# uC.net
KiCad netlist of a schematic drawn in Altium Designer
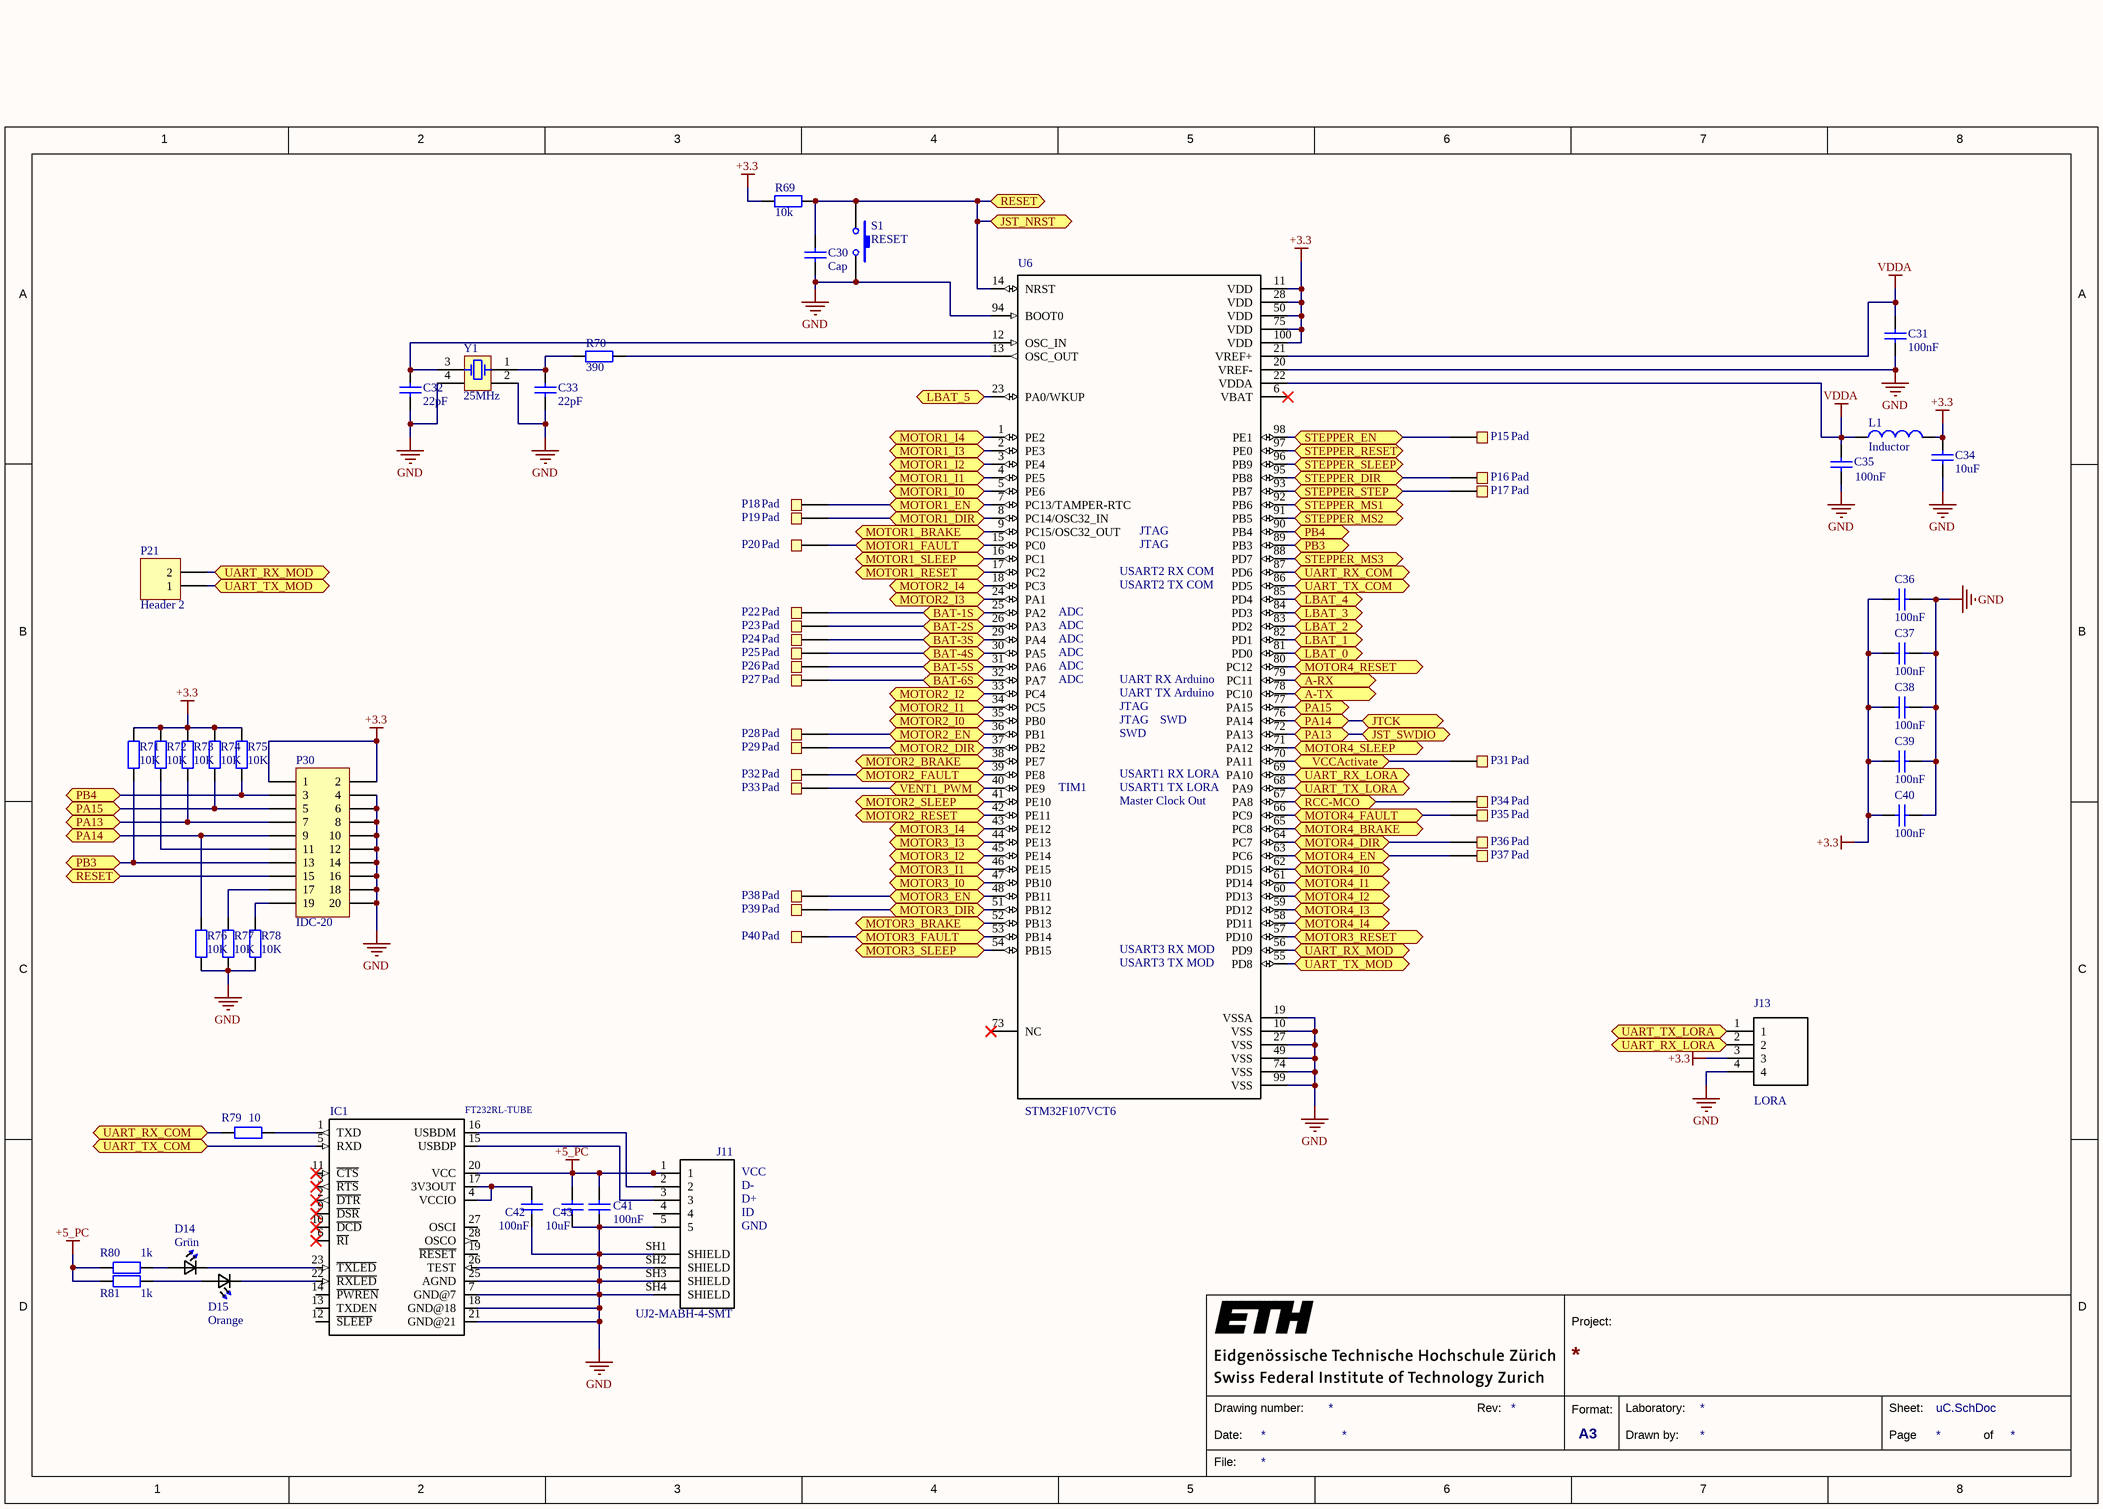
[diagram p0: uC.SchDoc]

(export (version "E")
  (design (tool "Eeschema 10.0.6"))
  (components
    (comp (ref "C30")
      (value "Cap")
      (footprint "CAP_0603i_1608m -N")
      (description "capacitor")
      (libsource (lib "IDSC std generic parts") (part "Cap"))
    )
    (comp (ref "C31")
      (value "100nF")
      (footprint "CAP_0603i_1608m -N")
      (description "capacitor")
      (libsource (lib "IDSC std generic parts") (part "Cap"))
    )
    (comp (ref "C32")
      (value "22pF")
      (footprint "CAP_0603i_1608m -N")
      (description "capacitor")
      (libsource (lib "IDSC std generic parts") (part "Cap"))
    )
    (comp (ref "C33")
      (value "22pF")
      (footprint "CAP_0603i_1608m -N")
      (description "capacitor")
      (libsource (lib "IDSC std generic parts") (part "Cap"))
    )
    (comp (ref "C34")
      (value "10uF")
      (footprint "CAP_0805i_2012m -N")
      (description "capacitor")
      (libsource (lib "IDSC std generic parts") (part "Cap"))
    )
    (comp (ref "C35")
      (value "100nF")
      (footprint "CAP_0603i_1608m -N")
      (description "capacitor")
      (libsource (lib "IDSC std generic parts") (part "Cap"))
    )
    (comp (ref "C36")
      (value "100nF")
      (footprint "CAP_0603i_1608m -N")
      (description "capacitor")
      (libsource (lib "IDSC std generic parts") (part "Cap"))
    )
    (comp (ref "C37")
      (value "100nF")
      (footprint "CAP_0603i_1608m -N")
      (description "capacitor")
      (libsource (lib "IDSC std generic parts") (part "Cap"))
    )
    (comp (ref "C38")
      (value "100nF")
      (footprint "CAP_0603i_1608m -N")
      (description "capacitor")
      (libsource (lib "IDSC std generic parts") (part "Cap"))
    )
    (comp (ref "C39")
      (value "100nF")
      (footprint "CAP_0603i_1608m -N")
      (description "capacitor")
      (libsource (lib "IDSC std generic parts") (part "Cap"))
    )
    (comp (ref "C40")
      (value "100nF")
      (footprint "CAP_0603i_1608m -N")
      (description "capacitor")
      (libsource (lib "IDSC std generic parts") (part "Cap"))
    )
    (comp (ref "C41")
      (value "100nF")
      (footprint "CAP_0603i_1608m -L")
      (description "capacitor")
      (libsource (lib "IDSC std generic parts") (part "Cap"))
    )
    (comp (ref "C42")
      (value "100nF")
      (footprint "CAP_0603i_1608m -L")
      (description "capacitor")
      (libsource (lib "IDSC std generic parts") (part "Cap"))
    )
    (comp (ref "C43")
      (value "10uF")
      (footprint "CAP_0805i_2012m -L")
      (description "capacitor")
      (libsource (lib "IDSC std generic parts") (part "Cap"))
    )
    (comp (ref "D14")
      (value "Grün")
      (footprint "*0603")
      (description "LED; SMD; 0603; gr黱; 35mcd; 1.6x0.8x0.55mm; 130掳; 2梅2.V; 20mA")
      (fields (field (name "MP") "LTST-C191KGKT") (field (name "DIGI-KEY_PART_NUMBER") "160-1446-1-ND"))
      (libsource (lib "Funk") (part "LTST-C191KGKT"))
    )
    (comp (ref "D15")
      (value "Orange")
      (footprint "*0603")
      (description "LED; SMD; 0603; orange; 45-90mcd; 1.6x0.8x0.55mm; 130Â°; 2Ã·2.4V; 20mA")
      (fields (field (name "MP") "LTST-C191KFKT") (field (name "DIGI-KEY_PART_NUMBER") "160-1445-1-ND"))
      (libsource (lib "Funk") (part "LTST-C191KFKT"))
    )
    (comp (ref "IC1")
      (value "FT232RL-TUBE")
      (footprint "*SSOP28-LD")
      (description "USB-to-UART 1-CH 256byte FIFO 5V 28-Pin SSOP Tube")
      (fields (field (name "DIGI-KEY_PART_NUMBER") "768-1306-ND") (field (name "MF") "FTDI,"))
      (libsource (lib "Funk") (part "FT232RL-TUBE"))
    )
    (comp (ref "J11")
      (value "UJ2-MABH-4-SMT")
      (footprint "*CUI_UJ2-MABH-4-SMT_UJ2-MABH-4-SMT(Primary)")
      (description "Mini AB, USB 2.0, 1 A, Right Angle, Surface Mount _SMT_, USB Receptacle")
      (fields (field (name "DIGI-KEY_PART_NUMBER") "102-5890-1-ND") (field (name "MF") "CUI Inc."))
      (libsource (lib "Funk") (part "UJ2-MABH-4-SMT"))
    )
    (comp (ref "J13")
      (value "LORA")
      (footprint "*PHOENIX_1751264")
      (description "Conn; Term Blk; Screw; 4: 3.5 mm; 26-16 AWG; 10 A; 160 V; Solder; 2.5 kV; PA")
      (fields (field (name "MP") "1751264") (field (name "MF") "Phoenix Contact"))
      (libsource (lib "Funk") (part "Terminal 4 Pin"))
    )
    (comp (ref "L1")
      (value "Inductor")
      (footprint "IND_0603i_1608m -L")
      (libsource (lib "IDSC std generic parts") (part "Inductor"))
    )
    (comp (ref "P15")
      (value "Pad")
      (footprint "PIN1")
      (description "Single Pad or Testpoint")
      (libsource (lib "IDSC std connectors") (part "Pad"))
    )
    (comp (ref "P16")
      (value "Pad")
      (footprint "PIN1")
      (description "Single Pad or Testpoint")
      (libsource (lib "IDSC std connectors") (part "Pad"))
    )
    (comp (ref "P17")
      (value "Pad")
      (footprint "PIN1")
      (description "Single Pad or Testpoint")
      (libsource (lib "IDSC std connectors") (part "Pad"))
    )
    (comp (ref "P18")
      (value "Pad")
      (footprint "PIN1")
      (description "Single Pad or Testpoint")
      (libsource (lib "") (part "Pad_1"))
    )
    (comp (ref "P19")
      (value "Pad")
      (footprint "PIN1")
      (description "Single Pad or Testpoint")
      (libsource (lib "") (part "Pad_1"))
    )
    (comp (ref "P20")
      (value "Pad")
      (footprint "PIN1")
      (description "Single Pad or Testpoint")
      (libsource (lib "") (part "Pad_1"))
    )
    (comp (ref "P21")
      (value "Header 2")
      (footprint "3.5MM Phoenix Contact 1984617")
      (description "Header, 2-Pin")
      (libsource (lib "IDSC std connectors") (part "Header 2"))
    )
    (comp (ref "P22")
      (value "Pad")
      (footprint "PIN1")
      (description "Single Pad or Testpoint")
      (libsource (lib "") (part "Pad_1"))
    )
    (comp (ref "P23")
      (value "Pad")
      (footprint "PIN1")
      (description "Single Pad or Testpoint")
      (libsource (lib "") (part "Pad_1"))
    )
    (comp (ref "P24")
      (value "Pad")
      (footprint "PIN1")
      (description "Single Pad or Testpoint")
      (libsource (lib "") (part "Pad_1"))
    )
    (comp (ref "P25")
      (value "Pad")
      (footprint "PIN1")
      (description "Single Pad or Testpoint")
      (libsource (lib "") (part "Pad_1"))
    )
    (comp (ref "P26")
      (value "Pad")
      (footprint "PIN1")
      (description "Single Pad or Testpoint")
      (libsource (lib "") (part "Pad_1"))
    )
    (comp (ref "P27")
      (value "Pad")
      (footprint "PIN1")
      (description "Single Pad or Testpoint")
      (libsource (lib "") (part "Pad_1"))
    )
    (comp (ref "P28")
      (value "Pad")
      (footprint "PIN1")
      (description "Single Pad or Testpoint")
      (libsource (lib "") (part "Pad_1"))
    )
    (comp (ref "P29")
      (value "Pad")
      (footprint "PIN1")
      (description "Single Pad or Testpoint")
      (libsource (lib "") (part "Pad_1"))
    )
    (comp (ref "P30")
      (value "IDC-20")
      (footprint "IDC-20")
      (description "Connector; IDC, Male Header, Thru-Hole; 20 Position; Vertical; Pitch 2.54 mm; B")
      (libsource (lib "IDSC std connectors") (part "IDC-20"))
    )
    (comp (ref "P31")
      (value "Pad")
      (footprint "PIN1")
      (description "Single Pad or Testpoint")
      (libsource (lib "IDSC std connectors") (part "Pad"))
    )
    (comp (ref "P32")
      (value "Pad")
      (footprint "PIN1")
      (description "Single Pad or Testpoint")
      (libsource (lib "") (part "Pad_1"))
    )
    (comp (ref "P33")
      (value "Pad")
      (footprint "PIN1")
      (description "Single Pad or Testpoint")
      (libsource (lib "") (part "Pad_1"))
    )
    (comp (ref "P34")
      (value "Pad")
      (footprint "PIN1")
      (description "Single Pad or Testpoint")
      (libsource (lib "IDSC std connectors") (part "Pad"))
    )
    (comp (ref "P35")
      (value "Pad")
      (footprint "PIN1")
      (description "Single Pad or Testpoint")
      (libsource (lib "IDSC std connectors") (part "Pad"))
    )
    (comp (ref "P36")
      (value "Pad")
      (footprint "PIN1")
      (description "Single Pad or Testpoint")
      (libsource (lib "IDSC std connectors") (part "Pad"))
    )
    (comp (ref "P37")
      (value "Pad")
      (footprint "PIN1")
      (description "Single Pad or Testpoint")
      (libsource (lib "IDSC std connectors") (part "Pad"))
    )
    (comp (ref "P38")
      (value "Pad")
      (footprint "PIN1")
      (description "Single Pad or Testpoint")
      (libsource (lib "") (part "Pad_1"))
    )
    (comp (ref "P39")
      (value "Pad")
      (footprint "PIN1")
      (description "Single Pad or Testpoint")
      (libsource (lib "") (part "Pad_1"))
    )
    (comp (ref "P40")
      (value "Pad")
      (footprint "PIN1")
      (description "Single Pad or Testpoint")
      (libsource (lib "") (part "Pad_1"))
    )
    (comp (ref "R69")
      (value "10k")
      (footprint "RES_0805i_2012m -N")
      (description "Resistor")
      (libsource (lib "") (part "Res_2"))
    )
    (comp (ref "R70")
      (value "390")
      (footprint "RES_0805i_2012m -N")
      (description "Resistor")
      (libsource (lib "IDSC std generic parts") (part "Res"))
    )
    (comp (ref "R71")
      (value "10K")
      (footprint "RES_0603i_1608m -N")
      (description "Resistor")
      (libsource (lib "") (part "Res_1"))
    )
    (comp (ref "R72")
      (value "10K")
      (footprint "RES_0603i_1608m -N")
      (description "Resistor")
      (libsource (lib "") (part "Res_1"))
    )
    (comp (ref "R73")
      (value "10K")
      (footprint "RES_0603i_1608m -N")
      (description "Resistor")
      (libsource (lib "") (part "Res_1"))
    )
    (comp (ref "R74")
      (value "10K")
      (footprint "RES_0603i_1608m -N")
      (description "Resistor")
      (libsource (lib "") (part "Res_1"))
    )
    (comp (ref "R75")
      (value "10K")
      (footprint "RES_0603i_1608m -N")
      (description "Resistor")
      (libsource (lib "") (part "Res_1"))
    )
    (comp (ref "R76")
      (value "10K")
      (footprint "RES_0603i_1608m -N")
      (description "Resistor")
      (libsource (lib "") (part "Res_1"))
    )
    (comp (ref "R77")
      (value "10K")
      (footprint "RES_0603i_1608m -N")
      (description "Resistor")
      (libsource (lib "") (part "Res_1"))
    )
    (comp (ref "R78")
      (value "10K")
      (footprint "RES_0603i_1608m -N")
      (description "Resistor")
      (libsource (lib "") (part "Res_1"))
    )
    (comp (ref "R79")
      (value "10")
      (footprint "RES_0603i_1608m -N")
      (description "Resistor")
      (libsource (lib "IDSC std generic parts") (part "Res"))
    )
    (comp (ref "R80")
      (value "1k")
      (footprint "RES_0603i_1608m -N")
      (description "Resistor")
      (libsource (lib "IDSC std generic parts") (part "Res"))
    )
    (comp (ref "R81")
      (value "1k")
      (footprint "RES_0603i_1608m -N")
      (description "Resistor")
      (libsource (lib "IDSC std generic parts") (part "Res"))
    )
    (comp (ref "S1")
      (value "RESET")
      (footprint "B3SL-1002P")
      (description "Switch")
      (libsource (lib "IDSC std generic parts") (part "SW PB"))
    )
    (comp (ref "U6")
      (value "STM32F107VCT6")
      (footprint "*QFP50P1600X1600X160-100N")
      (description "STM32 Series 32-bit 256 kB Flash 64 kB RAM ARM Based Microcontroller -LQFP-100")
      (fields (field (name "MF") "STMicroelectronics"))
      (libsource (lib "Funk") (part "STM32F107VCT6_1"))
    )
    (comp (ref "Y1")
      (value "25MHz")
      (footprint "TSX-3225 2*2.5")
      (description "Industrial Ceramic Resonator")
      (libsource (lib "IDSC std generic parts") (part "XTAL3"))
    )
  )
  (nets
    (net (code "1") (name "+3.3") (class "Default")
      (node (ref "C34") (pin "2") (pinfunction "2_2") (pintype "passive"))
      (node (ref "C36") (pin "2") (pinfunction "2_2") (pintype "passive"))
      (node (ref "C37") (pin "2") (pinfunction "2_2") (pintype "passive"))
      (node (ref "C38") (pin "2") (pinfunction "2_2") (pintype "passive"))
      (node (ref "C39") (pin "2") (pinfunction "2_2") (pintype "passive"))
      (node (ref "C40") (pin "2") (pinfunction "2_2") (pintype "passive"))
      (node (ref "J13") (pin "3") (pinfunction "3_3") (pintype "passive"))
      (node (ref "L1") (pin "2") (pinfunction "2_2") (pintype "passive"))
      (node (ref "P30") (pin "1") (pinfunction "1_1") (pintype "passive"))
      (node (ref "P30") (pin "2") (pinfunction "2_2") (pintype "passive"))
      (node (ref "R69") (pin "1") (pinfunction "1_1") (pintype "passive"))
      (node (ref "R71") (pin "2") (pinfunction "2_2") (pintype "passive"))
      (node (ref "R72") (pin "2") (pinfunction "2_2") (pintype "passive"))
      (node (ref "R73") (pin "2") (pinfunction "2_2") (pintype "passive"))
      (node (ref "R74") (pin "2") (pinfunction "2_2") (pintype "passive"))
      (node (ref "R75") (pin "2") (pinfunction "2_2") (pintype "passive"))
      (node (ref "U6") (pin "100") (pinfunction "VDD_100") (pintype "power_in"))
      (node (ref "U6") (pin "11") (pinfunction "VDD_11") (pintype "power_in"))
      (node (ref "U6") (pin "28") (pinfunction "VDD_28") (pintype "power_in"))
      (node (ref "U6") (pin "50") (pinfunction "VDD_50") (pintype "power_in"))
      (node (ref "U6") (pin "75") (pinfunction "VDD_75") (pintype "power_in"))
    )
    (net (code "2") (name "+5_PC") (class "Default")
      (node (ref "C41") (pin "2") (pinfunction "2_2") (pintype "passive"))
      (node (ref "C43") (pin "2") (pinfunction "2_2") (pintype "passive"))
      (node (ref "IC1") (pin "20") (pinfunction "VCC_20") (pintype "power_in"))
      (node (ref "J11") (pin "1") (pinfunction "1_1") (pintype "passive"))
      (node (ref "R80") (pin "2") (pinfunction "2_2") (pintype "passive"))
      (node (ref "R81") (pin "2") (pinfunction "2_2") (pintype "passive"))
    )
    (net (code "3") (name "/A-RX") (class "Default")
      (node (ref "U6") (pin "79") (pinfunction "PC11_79") (pintype "bidirectional"))
    )
    (net (code "4") (name "/A-TX") (class "Default")
      (node (ref "U6") (pin "78") (pinfunction "PC10_78") (pintype "bidirectional"))
    )
    (net (code "5") (name "/BAT-1S") (class "Default")
      (node (ref "P22") (pin "1") (pinfunction "1_1") (pintype "passive"))
      (node (ref "U6") (pin "25") (pinfunction "PA2_25") (pintype "bidirectional"))
    )
    (net (code "6") (name "/BAT-2S") (class "Default")
      (node (ref "P23") (pin "1") (pinfunction "1_1") (pintype "passive"))
      (node (ref "U6") (pin "26") (pinfunction "PA3_26") (pintype "bidirectional"))
    )
    (net (code "7") (name "/BAT-3S") (class "Default")
      (node (ref "P24") (pin "1") (pinfunction "1_1") (pintype "passive"))
      (node (ref "U6") (pin "29") (pinfunction "PA4_29") (pintype "bidirectional"))
    )
    (net (code "8") (name "/BAT-4S") (class "Default")
      (node (ref "P25") (pin "1") (pinfunction "1_1") (pintype "passive"))
      (node (ref "U6") (pin "30") (pinfunction "PA5_30") (pintype "bidirectional"))
    )
    (net (code "9") (name "/BAT-5S") (class "Default")
      (node (ref "P26") (pin "1") (pinfunction "1_1") (pintype "passive"))
      (node (ref "U6") (pin "31") (pinfunction "PA6_31") (pintype "bidirectional"))
    )
    (net (code "10") (name "/BAT-6S") (class "Default")
      (node (ref "P27") (pin "1") (pinfunction "1_1") (pintype "passive"))
      (node (ref "U6") (pin "32") (pinfunction "PA7_32") (pintype "bidirectional"))
    )
    (net (code "11") (name "/JST_NRST") (class "Default")
      (node (ref "C30") (pin "2") (pinfunction "2_2") (pintype "passive"))
      (node (ref "P30") (pin "15") (pinfunction "15_15") (pintype "passive"))
      (node (ref "R69") (pin "2") (pinfunction "2_2") (pintype "passive"))
      (node (ref "S1") (pin "1") (pinfunction "1_1") (pintype "passive"))
      (node (ref "U6") (pin "14") (pinfunction "NRST_14") (pintype "bidirectional"))
    )
    (net (code "12") (name "/JST_SWDIO") (class "Default")
      (node (ref "P30") (pin "7") (pinfunction "7_7") (pintype "passive"))
      (node (ref "R73") (pin "1") (pinfunction "1_1") (pintype "passive"))
      (node (ref "U6") (pin "72") (pinfunction "PA13_72") (pintype "bidirectional"))
    )
    (net (code "13") (name "/JTCK") (class "Default")
      (node (ref "P30") (pin "9") (pinfunction "9_9") (pintype "passive"))
      (node (ref "R76") (pin "2") (pinfunction "2_2") (pintype "passive"))
      (node (ref "U6") (pin "76") (pinfunction "PA14_76") (pintype "bidirectional"))
    )
    (net (code "14") (name "/LBAT_0") (class "Default")
      (node (ref "U6") (pin "81") (pinfunction "PD0_81") (pintype "bidirectional"))
    )
    (net (code "15") (name "/LBAT_1") (class "Default")
      (node (ref "U6") (pin "82") (pinfunction "PD1_82") (pintype "bidirectional"))
    )
    (net (code "16") (name "/LBAT_2") (class "Default")
      (node (ref "U6") (pin "83") (pinfunction "PD2_83") (pintype "bidirectional"))
    )
    (net (code "17") (name "/LBAT_3") (class "Default")
      (node (ref "U6") (pin "84") (pinfunction "PD3_84") (pintype "bidirectional"))
    )
    (net (code "18") (name "/LBAT_4") (class "Default")
      (node (ref "U6") (pin "85") (pinfunction "PD4_85") (pintype "bidirectional"))
    )
    (net (code "19") (name "/LBAT_5") (class "Default")
      (node (ref "U6") (pin "23") (pinfunction "PA0/WKUP_23") (pintype "bidirectional"))
    )
    (net (code "20") (name "/MOTOR1_BRAKE") (class "Default")
      (node (ref "U6") (pin "9") (pinfunction "PC15/OSC32_OUT_9") (pintype "bidirectional"))
    )
    (net (code "21") (name "/MOTOR1_DIR") (class "Default")
      (node (ref "P19") (pin "1") (pinfunction "1_1") (pintype "passive"))
      (node (ref "U6") (pin "8") (pinfunction "PC14/OSC32_IN_8") (pintype "bidirectional"))
    )
    (net (code "22") (name "/MOTOR1_EN") (class "Default")
      (node (ref "P18") (pin "1") (pinfunction "1_1") (pintype "passive"))
      (node (ref "U6") (pin "7") (pinfunction "PC13/TAMPER-RTC_7") (pintype "bidirectional"))
    )
    (net (code "23") (name "/MOTOR1_FAULT") (class "Default")
      (node (ref "P20") (pin "1") (pinfunction "1_1") (pintype "passive"))
      (node (ref "U6") (pin "15") (pinfunction "PC0_15") (pintype "bidirectional"))
    )
    (net (code "24") (name "/MOTOR1_I0") (class "Default")
      (node (ref "U6") (pin "5") (pinfunction "PE6_5") (pintype "bidirectional"))
    )
    (net (code "25") (name "/MOTOR1_I1") (class "Default")
      (node (ref "U6") (pin "4") (pinfunction "PE5_4") (pintype "bidirectional"))
    )
    (net (code "26") (name "/MOTOR1_I2") (class "Default")
      (node (ref "U6") (pin "3") (pinfunction "PE4_3") (pintype "bidirectional"))
    )
    (net (code "27") (name "/MOTOR1_I3") (class "Default")
      (node (ref "U6") (pin "2") (pinfunction "PE3_2") (pintype "bidirectional"))
    )
    (net (code "28") (name "/MOTOR1_I4") (class "Default")
      (node (ref "U6") (pin "1") (pinfunction "PE2_1") (pintype "bidirectional"))
    )
    (net (code "29") (name "/MOTOR1_RESET") (class "Default")
      (node (ref "U6") (pin "17") (pinfunction "PC2_17") (pintype "bidirectional"))
    )
    (net (code "30") (name "/MOTOR1_SLEEP") (class "Default")
      (node (ref "U6") (pin "16") (pinfunction "PC1_16") (pintype "bidirectional"))
    )
    (net (code "31") (name "/MOTOR2_BRAKE") (class "Default")
      (node (ref "U6") (pin "38") (pinfunction "PE7_38") (pintype "bidirectional"))
    )
    (net (code "32") (name "/MOTOR2_DIR") (class "Default")
      (node (ref "P29") (pin "1") (pinfunction "1_1") (pintype "passive"))
      (node (ref "U6") (pin "37") (pinfunction "PB2_37") (pintype "bidirectional"))
    )
    (net (code "33") (name "/MOTOR2_EN") (class "Default")
      (node (ref "P28") (pin "1") (pinfunction "1_1") (pintype "passive"))
      (node (ref "U6") (pin "36") (pinfunction "PB1_36") (pintype "bidirectional"))
    )
    (net (code "34") (name "/MOTOR2_FAULT") (class "Default")
      (node (ref "P32") (pin "1") (pinfunction "1_1") (pintype "passive"))
      (node (ref "U6") (pin "39") (pinfunction "PE8_39") (pintype "bidirectional"))
    )
    (net (code "35") (name "/MOTOR2_I0") (class "Default")
      (node (ref "U6") (pin "35") (pinfunction "PB0_35") (pintype "bidirectional"))
    )
    (net (code "36") (name "/MOTOR2_I1") (class "Default")
      (node (ref "U6") (pin "34") (pinfunction "PC5_34") (pintype "bidirectional"))
    )
    (net (code "37") (name "/MOTOR2_I2") (class "Default")
      (node (ref "U6") (pin "33") (pinfunction "PC4_33") (pintype "bidirectional"))
    )
    (net (code "38") (name "/MOTOR2_I3") (class "Default")
      (node (ref "U6") (pin "24") (pinfunction "PA1_24") (pintype "bidirectional"))
    )
    (net (code "39") (name "/MOTOR2_I4") (class "Default")
      (node (ref "U6") (pin "18") (pinfunction "PC3_18") (pintype "bidirectional"))
    )
    (net (code "40") (name "/MOTOR2_RESET") (class "Default")
      (node (ref "U6") (pin "42") (pinfunction "PE11_42") (pintype "bidirectional"))
    )
    (net (code "41") (name "/MOTOR2_SLEEP") (class "Default")
      (node (ref "U6") (pin "41") (pinfunction "PE10_41") (pintype "bidirectional"))
    )
    (net (code "42") (name "/MOTOR3_BRAKE") (class "Default")
      (node (ref "U6") (pin "52") (pinfunction "PB13_52") (pintype "bidirectional"))
    )
    (net (code "43") (name "/MOTOR3_DIR") (class "Default")
      (node (ref "P39") (pin "1") (pinfunction "1_1") (pintype "passive"))
      (node (ref "U6") (pin "51") (pinfunction "PB12_51") (pintype "bidirectional"))
    )
    (net (code "44") (name "/MOTOR3_EN") (class "Default")
      (node (ref "P38") (pin "1") (pinfunction "1_1") (pintype "passive"))
      (node (ref "U6") (pin "48") (pinfunction "PB11_48") (pintype "bidirectional"))
    )
    (net (code "45") (name "/MOTOR3_FAULT") (class "Default")
      (node (ref "P40") (pin "1") (pinfunction "1_1") (pintype "passive"))
      (node (ref "U6") (pin "53") (pinfunction "PB14_53") (pintype "bidirectional"))
    )
    (net (code "46") (name "/MOTOR3_I0") (class "Default")
      (node (ref "U6") (pin "47") (pinfunction "PB10_47") (pintype "bidirectional"))
    )
    (net (code "47") (name "/MOTOR3_I1") (class "Default")
      (node (ref "U6") (pin "46") (pinfunction "PE15_46") (pintype "bidirectional"))
    )
    (net (code "48") (name "/MOTOR3_I2") (class "Default")
      (node (ref "U6") (pin "45") (pinfunction "PE14_45") (pintype "bidirectional"))
    )
    (net (code "49") (name "/MOTOR3_I3") (class "Default")
      (node (ref "U6") (pin "44") (pinfunction "PE13_44") (pintype "bidirectional"))
    )
    (net (code "50") (name "/MOTOR3_I4") (class "Default")
      (node (ref "U6") (pin "43") (pinfunction "PE12_43") (pintype "bidirectional"))
    )
    (net (code "51") (name "/MOTOR3_RESET") (class "Default")
      (node (ref "U6") (pin "57") (pinfunction "PD10_57") (pintype "bidirectional"))
    )
    (net (code "52") (name "/MOTOR3_SLEEP") (class "Default")
      (node (ref "U6") (pin "54") (pinfunction "PB15_54") (pintype "bidirectional"))
    )
    (net (code "53") (name "/MOTOR4_BRAKE") (class "Default")
      (node (ref "U6") (pin "65") (pinfunction "PC8_65") (pintype "bidirectional"))
    )
    (net (code "54") (name "/MOTOR4_DIR") (class "Default")
      (node (ref "P36") (pin "1") (pinfunction "1_1") (pintype "passive"))
      (node (ref "U6") (pin "64") (pinfunction "PC7_64") (pintype "bidirectional"))
    )
    (net (code "55") (name "/MOTOR4_EN") (class "Default")
      (node (ref "P37") (pin "1") (pinfunction "1_1") (pintype "passive"))
      (node (ref "U6") (pin "63") (pinfunction "PC6_63") (pintype "bidirectional"))
    )
    (net (code "56") (name "/MOTOR4_FAULT") (class "Default")
      (node (ref "P35") (pin "1") (pinfunction "1_1") (pintype "passive"))
      (node (ref "U6") (pin "66") (pinfunction "PC9_66") (pintype "bidirectional"))
    )
    (net (code "57") (name "/MOTOR4_I0") (class "Default")
      (node (ref "U6") (pin "62") (pinfunction "PD15_62") (pintype "bidirectional"))
    )
    (net (code "58") (name "/MOTOR4_I1") (class "Default")
      (node (ref "U6") (pin "61") (pinfunction "PD14_61") (pintype "bidirectional"))
    )
    (net (code "59") (name "/MOTOR4_I2") (class "Default")
      (node (ref "U6") (pin "60") (pinfunction "PD13_60") (pintype "bidirectional"))
    )
    (net (code "60") (name "/MOTOR4_I3") (class "Default")
      (node (ref "U6") (pin "59") (pinfunction "PD12_59") (pintype "bidirectional"))
    )
    (net (code "61") (name "/MOTOR4_I4") (class "Default")
      (node (ref "U6") (pin "58") (pinfunction "PD11_58") (pintype "bidirectional"))
    )
    (net (code "62") (name "/MOTOR4_RESET") (class "Default")
      (node (ref "U6") (pin "80") (pinfunction "PC12_80") (pintype "bidirectional"))
    )
    (net (code "63") (name "/MOTOR4_SLEEP") (class "Default")
      (node (ref "U6") (pin "71") (pinfunction "PA12_71") (pintype "bidirectional"))
    )
    (net (code "64") (name "/PA15") (class "Default")
      (node (ref "P30") (pin "5") (pinfunction "5_5") (pintype "passive"))
      (node (ref "R74") (pin "1") (pinfunction "1_1") (pintype "passive"))
      (node (ref "U6") (pin "77") (pinfunction "PA15_77") (pintype "bidirectional"))
    )
    (net (code "65") (name "/PB3") (class "Default")
      (node (ref "P30") (pin "13") (pinfunction "13_13") (pintype "passive"))
      (node (ref "R71") (pin "1") (pinfunction "1_1") (pintype "passive"))
      (node (ref "U6") (pin "89") (pinfunction "PB3_89") (pintype "bidirectional"))
    )
    (net (code "66") (name "/PB4") (class "Default")
      (node (ref "P30") (pin "3") (pinfunction "3_3") (pintype "passive"))
      (node (ref "R75") (pin "1") (pinfunction "1_1") (pintype "passive"))
      (node (ref "U6") (pin "90") (pinfunction "PB4_90") (pintype "bidirectional"))
    )
    (net (code "67") (name "/RCC-MCO") (class "Default")
      (node (ref "P34") (pin "1") (pinfunction "1_1") (pintype "passive"))
      (node (ref "U6") (pin "67") (pinfunction "PA8_67") (pintype "bidirectional"))
    )
    (net (code "68") (name "/STEPPER_DIR") (class "Default")
      (node (ref "P16") (pin "1") (pinfunction "1_1") (pintype "passive"))
      (node (ref "U6") (pin "95") (pinfunction "PB8_95") (pintype "bidirectional"))
    )
    (net (code "69") (name "/STEPPER_EN") (class "Default")
      (node (ref "P15") (pin "1") (pinfunction "1_1") (pintype "passive"))
      (node (ref "U6") (pin "98") (pinfunction "PE1_98") (pintype "bidirectional"))
    )
    (net (code "70") (name "/STEPPER_MS1") (class "Default")
      (node (ref "U6") (pin "92") (pinfunction "PB6_92") (pintype "bidirectional"))
    )
    (net (code "71") (name "/STEPPER_MS2") (class "Default")
      (node (ref "U6") (pin "91") (pinfunction "PB5_91") (pintype "bidirectional"))
    )
    (net (code "72") (name "/STEPPER_MS3") (class "Default")
      (node (ref "U6") (pin "88") (pinfunction "PD7_88") (pintype "bidirectional"))
    )
    (net (code "73") (name "/STEPPER_RESET") (class "Default")
      (node (ref "U6") (pin "97") (pinfunction "PE0_97") (pintype "bidirectional"))
    )
    (net (code "74") (name "/STEPPER_SLEEP") (class "Default")
      (node (ref "U6") (pin "96") (pinfunction "PB9_96") (pintype "bidirectional"))
    )
    (net (code "75") (name "/STEPPER_STEP") (class "Default")
      (node (ref "P17") (pin "1") (pinfunction "1_1") (pintype "passive"))
      (node (ref "U6") (pin "93") (pinfunction "PB7_93") (pintype "bidirectional"))
    )
    (net (code "76") (name "/UART_RX_COM") (class "Default")
      (node (ref "R79") (pin "2") (pinfunction "2_2") (pintype "passive"))
      (node (ref "U6") (pin "87") (pinfunction "PD6_87") (pintype "bidirectional"))
    )
    (net (code "77") (name "/UART_RX_LORA") (class "Default")
      (node (ref "J13") (pin "2") (pinfunction "2_2") (pintype "passive"))
      (node (ref "U6") (pin "69") (pinfunction "PA10_69") (pintype "bidirectional"))
    )
    (net (code "78") (name "/UART_RX_MOD") (class "Default")
      (node (ref "P21") (pin "2") (pinfunction "2_2") (pintype "passive"))
      (node (ref "U6") (pin "56") (pinfunction "PD9_56") (pintype "bidirectional"))
    )
    (net (code "79") (name "/UART_TX_COM") (class "Default")
      (node (ref "IC1") (pin "5") (pinfunction "RXD_5") (pintype "input"))
      (node (ref "U6") (pin "86") (pinfunction "PD5_86") (pintype "bidirectional"))
    )
    (net (code "80") (name "/UART_TX_LORA") (class "Default")
      (node (ref "J13") (pin "1") (pinfunction "1_1") (pintype "passive"))
      (node (ref "U6") (pin "68") (pinfunction "PA9_68") (pintype "bidirectional"))
    )
    (net (code "81") (name "/UART_TX_MOD") (class "Default")
      (node (ref "P21") (pin "1") (pinfunction "1_1") (pintype "passive"))
      (node (ref "U6") (pin "55") (pinfunction "PD8_55") (pintype "bidirectional"))
    )
    (net (code "82") (name "/VCCActivate") (class "Default")
      (node (ref "P31") (pin "1") (pinfunction "1_1") (pintype "passive"))
      (node (ref "U6") (pin "70") (pinfunction "PA11_70") (pintype "bidirectional"))
    )
    (net (code "83") (name "/VENT1_PWM") (class "Default")
      (node (ref "P33") (pin "1") (pinfunction "1_1") (pintype "passive"))
      (node (ref "U6") (pin "40") (pinfunction "PE9_40") (pintype "bidirectional"))
    )
    (net (code "84") (name "GND") (class "Default")
      (node (ref "C30") (pin "1") (pinfunction "1_1") (pintype "passive"))
      (node (ref "C31") (pin "1") (pinfunction "1_1") (pintype "passive"))
      (node (ref "C32") (pin "1") (pinfunction "1_1") (pintype "passive"))
      (node (ref "C33") (pin "1") (pinfunction "1_1") (pintype "passive"))
      (node (ref "C34") (pin "1") (pinfunction "1_1") (pintype "passive"))
      (node (ref "C35") (pin "1") (pinfunction "1_1") (pintype "passive"))
      (node (ref "C36") (pin "1") (pinfunction "1_1") (pintype "passive"))
      (node (ref "C37") (pin "1") (pinfunction "1_1") (pintype "passive"))
      (node (ref "C38") (pin "1") (pinfunction "1_1") (pintype "passive"))
      (node (ref "C39") (pin "1") (pinfunction "1_1") (pintype "passive"))
      (node (ref "C40") (pin "1") (pinfunction "1_1") (pintype "passive"))
      (node (ref "C41") (pin "1") (pinfunction "1_1") (pintype "passive"))
      (node (ref "C42") (pin "1") (pinfunction "1_1") (pintype "passive"))
      (node (ref "C43") (pin "1") (pinfunction "1_1") (pintype "passive"))
      (node (ref "IC1") (pin "18") (pinfunction "GND@18_18") (pintype "power_in"))
      (node (ref "IC1") (pin "21") (pinfunction "GND@21_21") (pintype "power_in"))
      (node (ref "IC1") (pin "25") (pinfunction "AGND_25") (pintype "power_in"))
      (node (ref "IC1") (pin "26") (pinfunction "TEST_26") (pintype "input"))
      (node (ref "IC1") (pin "7") (pinfunction "GND@7_7") (pintype "power_in"))
      (node (ref "J11") (pin "5") (pinfunction "5_5") (pintype "passive"))
      (node (ref "J11") (pin "SH1") (pinfunction "SHIELD_SH1") (pintype "passive"))
      (node (ref "J11") (pin "SH2") (pinfunction "SHIELD_SH2") (pintype "passive"))
      (node (ref "J11") (pin "SH3") (pinfunction "SHIELD_SH3") (pintype "passive"))
      (node (ref "J11") (pin "SH4") (pinfunction "SHIELD_SH4") (pintype "passive"))
      (node (ref "J13") (pin "4") (pinfunction "4_4") (pintype "passive"))
      (node (ref "P30") (pin "10") (pinfunction "10_10") (pintype "passive"))
      (node (ref "P30") (pin "12") (pinfunction "12_12") (pintype "passive"))
      (node (ref "P30") (pin "14") (pinfunction "14_14") (pintype "passive"))
      (node (ref "P30") (pin "16") (pinfunction "16_16") (pintype "passive"))
      (node (ref "P30") (pin "18") (pinfunction "18_18") (pintype "passive"))
      (node (ref "P30") (pin "20") (pinfunction "20_20") (pintype "passive"))
      (node (ref "P30") (pin "4") (pinfunction "4_4") (pintype "passive"))
      (node (ref "P30") (pin "6") (pinfunction "6_6") (pintype "passive"))
      (node (ref "P30") (pin "8") (pinfunction "8_8") (pintype "passive"))
      (node (ref "R76") (pin "1") (pinfunction "1_1") (pintype "passive"))
      (node (ref "R77") (pin "1") (pinfunction "1_1") (pintype "passive"))
      (node (ref "R78") (pin "1") (pinfunction "1_1") (pintype "passive"))
      (node (ref "S1") (pin "2") (pinfunction "2_2") (pintype "passive"))
      (node (ref "U6") (pin "10") (pinfunction "VSS_10") (pintype "power_in"))
      (node (ref "U6") (pin "19") (pinfunction "VSSA_19") (pintype "power_in"))
      (node (ref "U6") (pin "20") (pinfunction "VREF-_20") (pintype "power_in"))
      (node (ref "U6") (pin "27") (pinfunction "VSS_27") (pintype "power_in"))
      (node (ref "U6") (pin "49") (pinfunction "VSS_49") (pintype "power_in"))
      (node (ref "U6") (pin "74") (pinfunction "VSS_74") (pintype "power_in"))
      (node (ref "U6") (pin "94") (pinfunction "BOOT0_94") (pintype "input"))
      (node (ref "U6") (pin "99") (pinfunction "VSS_99") (pintype "power_in"))
      (node (ref "Y1") (pin "2") (pinfunction "COM_2") (pintype "passive"))
      (node (ref "Y1") (pin "4") (pinfunction "COM_4") (pintype "passive"))
    )
    (net (code "85") (name "Net-(D14-A2)") (class "Default")
      (node (ref "D14") (pin "2") (pinfunction "A2_2") (pintype "passive"))
      (node (ref "R80") (pin "1") (pinfunction "1_1") (pintype "passive"))
    )
    (net (code "86") (name "Net-(D14-K2)") (class "Default")
      (node (ref "D14") (pin "1") (pinfunction "K2_1") (pintype "passive"))
      (node (ref "IC1") (pin "23") (pinfunction "~{TXLED}_23") (pintype "input"))
    )
    (net (code "87") (name "Net-(D15-A2)") (class "Default")
      (node (ref "D15") (pin "2") (pinfunction "A2_2") (pintype "passive"))
      (node (ref "R81") (pin "1") (pinfunction "1_1") (pintype "passive"))
    )
    (net (code "88") (name "Net-(D15-K2)") (class "Default")
      (node (ref "D15") (pin "1") (pinfunction "K2_1") (pintype "passive"))
      (node (ref "IC1") (pin "22") (pinfunction "~{RXLED}_22") (pintype "input"))
    )
    (net (code "89") (name "Net-(IC1-3V3OUT)") (class "Default")
      (node (ref "C42") (pin "2") (pinfunction "2_2") (pintype "passive"))
      (node (ref "IC1") (pin "17") (pinfunction "3V3OUT_17") (pintype "power_in"))
      (node (ref "IC1") (pin "4") (pinfunction "VCCIO_4") (pintype "power_in"))
    )
    (net (code "90") (name "Net-(IC1-TXD)") (class "Default")
      (node (ref "IC1") (pin "1") (pinfunction "TXD_1") (pintype "output"))
      (node (ref "R79") (pin "1") (pinfunction "1_1") (pintype "passive"))
    )
    (net (code "91") (name "Net-(IC1-USBDM)") (class "Default")
      (node (ref "IC1") (pin "16") (pinfunction "USBDM_16") (pintype "bidirectional"))
      (node (ref "J11") (pin "2") (pinfunction "2_2") (pintype "passive"))
    )
    (net (code "92") (name "Net-(IC1-USBDP)") (class "Default")
      (node (ref "IC1") (pin "15") (pinfunction "USBDP_15") (pintype "bidirectional"))
      (node (ref "J11") (pin "3") (pinfunction "3_3") (pintype "passive"))
    )
    (net (code "93") (name "Net-(P30-Pad11)") (class "Default")
      (node (ref "P30") (pin "11") (pinfunction "11_11") (pintype "passive"))
      (node (ref "R72") (pin "1") (pinfunction "1_1") (pintype "passive"))
    )
    (net (code "94") (name "Net-(P30-Pad17)") (class "Default")
      (node (ref "P30") (pin "17") (pinfunction "17_17") (pintype "passive"))
      (node (ref "R77") (pin "2") (pinfunction "2_2") (pintype "passive"))
    )
    (net (code "95") (name "Net-(P30-Pad19)") (class "Default")
      (node (ref "P30") (pin "19") (pinfunction "19_19") (pintype "passive"))
      (node (ref "R78") (pin "2") (pinfunction "2_2") (pintype "passive"))
    )
    (net (code "96") (name "Net-(U6-OSC_IN)") (class "Default")
      (node (ref "C32") (pin "2") (pinfunction "2_2") (pintype "passive"))
      (node (ref "U6") (pin "12") (pinfunction "OSC_IN_12") (pintype "input"))
      (node (ref "Y1") (pin "3") (pinfunction "OSC2_3") (pintype "passive"))
    )
    (net (code "97") (name "Net-(U6-OSC_OUT)") (class "Default")
      (node (ref "R70") (pin "1") (pinfunction "1_1") (pintype "passive"))
      (node (ref "U6") (pin "13") (pinfunction "OSC_OUT_13") (pintype "output"))
    )
    (net (code "98") (name "Net-(Y1-OSC1)") (class "Default")
      (node (ref "C33") (pin "2") (pinfunction "2_2") (pintype "passive"))
      (node (ref "R70") (pin "2") (pinfunction "2_2") (pintype "passive"))
      (node (ref "Y1") (pin "1") (pinfunction "OSC1_1") (pintype "passive"))
    )
    (net (code "99") (name "VDDA") (class "Default")
      (node (ref "C31") (pin "2") (pinfunction "2_2") (pintype "passive"))
      (node (ref "C35") (pin "2") (pinfunction "2_2") (pintype "passive"))
      (node (ref "L1") (pin "1") (pinfunction "1_1") (pintype "passive"))
      (node (ref "U6") (pin "21") (pinfunction "VREF+_21") (pintype "power_in"))
      (node (ref "U6") (pin "22") (pinfunction "VDDA_22") (pintype "power_in"))
    )
    (net (code "100") (name "unconnected-(IC1-OSCI-Pad27)") (class "Default")
      (node (ref "IC1") (pin "27") (pinfunction "OSCI_27") (pintype "passive"))
    )
    (net (code "101") (name "unconnected-(IC1-OSCO-Pad28)") (class "Default")
      (node (ref "IC1") (pin "28") (pinfunction "OSCO_28") (pintype "output"))
    )
    (net (code "102") (name "unconnected-(IC1-TXDEN-Pad13)") (class "Default")
      (node (ref "IC1") (pin "13") (pinfunction "TXDEN_13") (pintype "passive"))
    )
    (net (code "103") (name "unconnected-(IC1-~{CTS}-Pad11)") (class "Default")
      (node (ref "IC1") (pin "11") (pinfunction "~{CTS}_11") (pintype "input+no_connect"))
    )
    (net (code "104") (name "unconnected-(IC1-~{DCD}-Pad10)") (class "Default")
      (node (ref "IC1") (pin "10") (pinfunction "~{DCD}_10") (pintype "passive+no_connect"))
    )
    (net (code "105") (name "unconnected-(IC1-~{DSR}-Pad9)") (class "Default")
      (node (ref "IC1") (pin "9") (pinfunction "~{DSR}_9") (pintype "passive+no_connect"))
    )
    (net (code "106") (name "unconnected-(IC1-~{DTR}-Pad2)") (class "Default")
      (node (ref "IC1") (pin "2") (pinfunction "~{DTR}_2") (pintype "output+no_connect"))
    )
    (net (code "107") (name "unconnected-(IC1-~{PWREN}-Pad14)") (class "Default")
      (node (ref "IC1") (pin "14") (pinfunction "~{PWREN}_14") (pintype "passive"))
    )
    (net (code "108") (name "unconnected-(IC1-~{RESET}-Pad19)") (class "Default")
      (node (ref "IC1") (pin "19") (pinfunction "~{RESET}_19") (pintype "passive"))
    )
    (net (code "109") (name "unconnected-(IC1-~{RI}-Pad6)") (class "Default")
      (node (ref "IC1") (pin "6") (pinfunction "~{RI}_6") (pintype "passive+no_connect"))
    )
    (net (code "110") (name "unconnected-(IC1-~{RTS}-Pad3)") (class "Default")
      (node (ref "IC1") (pin "3") (pinfunction "~{RTS}_3") (pintype "output+no_connect"))
    )
    (net (code "111") (name "unconnected-(IC1-~{SLEEP}-Pad12)") (class "Default")
      (node (ref "IC1") (pin "12") (pinfunction "~{SLEEP}_12") (pintype "passive"))
    )
    (net (code "112") (name "unconnected-(J11-Pad4)") (class "Default")
      (node (ref "J11") (pin "4") (pinfunction "4_4") (pintype "passive"))
    )
    (net (code "113") (name "unconnected-(U6-NC-Pad73)") (class "Default")
      (node (ref "U6") (pin "73") (pinfunction "NC_73") (pintype "passive+no_connect"))
    )
    (net (code "114") (name "unconnected-(U6-VBAT-Pad6)") (class "Default")
      (node (ref "U6") (pin "6") (pinfunction "VBAT_6") (pintype "power_in+no_connect"))
    )
  )
)
